# Kivipallur_joonis3.net
KiCad netlist of a schematic drawn in Altium Designer
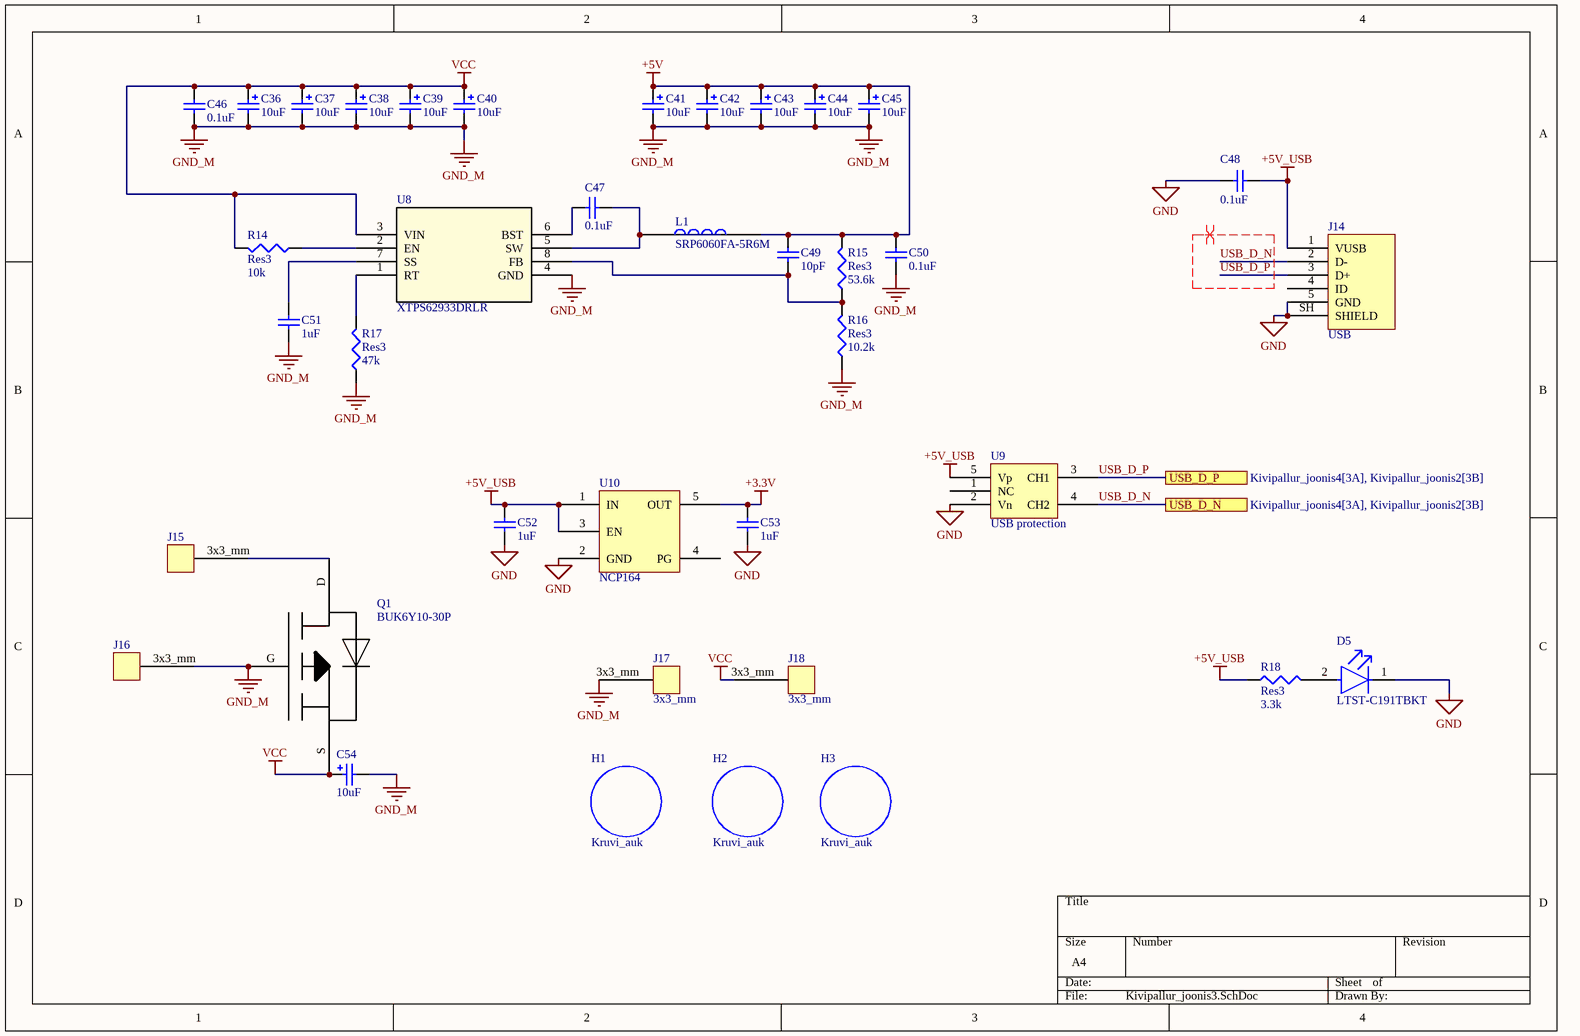
[diagram p0: Kivipallur_joonis3.SchDoc]

(export (version "E")
  (design (tool "Eeschema 10.0.6"))
  (components
    (comp (ref "C36")
      (value "10uF")
      (footprint "C0805")
      (description "Polarized Capacitor (Surface Mount)")
      (fields (field (name "Comment") "Cap Pol3") (field (name "PUBLISHER") "Altium Limited"))
      (libsource (lib "Miscellaneous Devices") (part "Cap Pol3"))
    )
    (comp (ref "C37")
      (value "10uF")
      (footprint "C0805")
      (description "Polarized Capacitor (Surface Mount)")
      (fields (field (name "Comment") "Cap Pol3") (field (name "PUBLISHER") "Altium Limited"))
      (libsource (lib "Miscellaneous Devices") (part "Cap Pol3"))
    )
    (comp (ref "C38")
      (value "10uF")
      (footprint "C0805")
      (description "Polarized Capacitor (Surface Mount)")
      (fields (field (name "Comment") "Cap Pol3") (field (name "PUBLISHER") "Altium Limited"))
      (libsource (lib "Miscellaneous Devices") (part "Cap Pol3"))
    )
    (comp (ref "C39")
      (value "10uF")
      (footprint "C0805")
      (description "Polarized Capacitor (Surface Mount)")
      (fields (field (name "Comment") "Cap Pol3") (field (name "PUBLISHER") "Altium Limited"))
      (libsource (lib "Miscellaneous Devices") (part "Cap Pol3"))
    )
    (comp (ref "C40")
      (value "10uF")
      (footprint "C0805")
      (description "Polarized Capacitor (Surface Mount)")
      (fields (field (name "Comment") "Cap Pol3") (field (name "PUBLISHER") "Altium Limited"))
      (libsource (lib "Miscellaneous Devices") (part "Cap Pol3"))
    )
    (comp (ref "C41")
      (value "10uF")
      (footprint "C0805")
      (description "Polarized Capacitor (Surface Mount)")
      (fields (field (name "Comment") "Cap Pol3") (field (name "PUBLISHER") "Altium Limited"))
      (libsource (lib "Miscellaneous Devices") (part "Cap Pol3"))
    )
    (comp (ref "C42")
      (value "10uF")
      (footprint "C0805")
      (description "Polarized Capacitor (Surface Mount)")
      (fields (field (name "Comment") "Cap Pol3") (field (name "PUBLISHER") "Altium Limited"))
      (libsource (lib "Miscellaneous Devices") (part "Cap Pol3"))
    )
    (comp (ref "C43")
      (value "10uF")
      (footprint "C0805")
      (description "Polarized Capacitor (Surface Mount)")
      (fields (field (name "Comment") "Cap Pol3") (field (name "PUBLISHER") "Altium Limited"))
      (libsource (lib "Miscellaneous Devices") (part "Cap Pol3"))
    )
    (comp (ref "C44")
      (value "10uF")
      (footprint "C0805")
      (description "Polarized Capacitor (Surface Mount)")
      (fields (field (name "Comment") "Cap Pol3") (field (name "PUBLISHER") "Altium Limited"))
      (libsource (lib "Miscellaneous Devices") (part "Cap Pol3"))
    )
    (comp (ref "C45")
      (value "10uF")
      (footprint "C0805")
      (description "Polarized Capacitor (Surface Mount)")
      (fields (field (name "Comment") "Cap Pol3") (field (name "PUBLISHER") "Altium Limited"))
      (libsource (lib "Miscellaneous Devices") (part "Cap Pol3"))
    )
    (comp (ref "C46")
      (value "0.1uF")
      (footprint "1608[0603]")
      (description "Capacitor (Semiconductor SIM Model)")
      (fields (field (name "Comment") "Cap Semi") (field (name "PUBLISHER") "Altium Limited"))
      (libsource (lib "Miscellaneous Devices") (part "Cap Semi"))
    )
    (comp (ref "C47")
      (value "0.1uF")
      (footprint "1608[0603]")
      (description "Capacitor (Semiconductor SIM Model)")
      (fields (field (name "Comment") "Cap Semi") (field (name "PUBLISHER") "Altium Limited"))
      (libsource (lib "Miscellaneous Devices") (part "Cap Semi"))
    )
    (comp (ref "C48")
      (value "0.1uF")
      (footprint "1608[0603]")
      (description "Capacitor (Semiconductor SIM Model)")
      (fields (field (name "Comment") "Cap Semi") (field (name "PUBLISHER") "Altium Limited"))
      (libsource (lib "Miscellaneous Devices") (part "Cap Semi"))
    )
    (comp (ref "C49")
      (value "10pF")
      (footprint "1608[0603]")
      (description "Capacitor (Semiconductor SIM Model)")
      (fields (field (name "Comment") "Cap Semi") (field (name "PUBLISHER") "Altium Limited"))
      (libsource (lib "Miscellaneous Devices") (part "Cap Semi"))
    )
    (comp (ref "C50")
      (value "0.1uF")
      (footprint "1608[0603]")
      (description "Capacitor (Semiconductor SIM Model)")
      (fields (field (name "Comment") "Cap Semi") (field (name "PUBLISHER") "Altium Limited"))
      (libsource (lib "Miscellaneous Devices") (part "Cap Semi"))
    )
    (comp (ref "C51")
      (value "1uF")
      (footprint "1608[0603]")
      (description "Capacitor (Semiconductor SIM Model)")
      (fields (field (name "Comment") "Cap Semi") (field (name "PUBLISHER") "Altium Limited"))
      (libsource (lib "Miscellaneous Devices") (part "Cap Semi"))
    )
    (comp (ref "C52")
      (value "1uF")
      (footprint "1608[0603]")
      (description "Capacitor (Semiconductor SIM Model)")
      (fields (field (name "Comment") "Cap Semi") (field (name "PUBLISHER") "Altium Limited"))
      (libsource (lib "Miscellaneous Devices") (part "Cap Semi"))
    )
    (comp (ref "C53")
      (value "1uF")
      (footprint "1608[0603]")
      (description "Capacitor (Semiconductor SIM Model)")
      (fields (field (name "Comment") "Cap Semi") (field (name "PUBLISHER") "Altium Limited"))
      (libsource (lib "Miscellaneous Devices") (part "Cap Semi"))
    )
    (comp (ref "C54")
      (value "10uF")
      (footprint "C0805")
      (description "Polarized Capacitor (Surface Mount)")
      (fields (field (name "Comment") "Cap Pol3") (field (name "PUBLISHER") "Altium Limited"))
      (libsource (lib "Miscellaneous Devices") (part "Cap Pol3"))
    )
    (comp (ref "D5")
      (value "LTST-C191TBKT")
      (footprint "FP-LTST-C191TBKT-MFG")
      (description "LED BLUE CLEAR CHIP SMD")
      (libsource (lib "Altium Content Vault") (part "8706943c75ba83719d021d2fdc84c58"))
    )
    (comp (ref "H1")
      (value "Kruvi_auk")
      (footprint "kruvi_auk")
      (libsource (lib "kruvi_auk") (part "Kruvi_auk"))
    )
    (comp (ref "H2")
      (value "Kruvi_auk")
      (footprint "kruvi_auk")
      (libsource (lib "kruvi_auk") (part "Kruvi_auk"))
    )
    (comp (ref "H3")
      (value "Kruvi_auk")
      (footprint "kruvi_auk")
      (libsource (lib "kruvi_auk") (part "Kruvi_auk"))
    )
    (comp (ref "J14") (value "USB") (footprint "USB") (libsource (lib "USB") (part "USB")))
    (comp (ref "J15") (value "3x3_mm") (footprint "3x3_mm") (libsource (lib "") (part "3x3_mm_1")))
    (comp (ref "J16") (value "3x3_mm") (footprint "3x3_mm") (libsource (lib "") (part "3x3_mm_1")))
    (comp (ref "J17") (value "3x3_mm") (footprint "3x3_mm") (libsource (lib "3x3_mm") (part "3x3_mm")))
    (comp (ref "J18") (value "3x3_mm") (footprint "3x3_mm") (libsource (lib "3x3_mm") (part "3x3_mm")))
    (comp (ref "L1")
      (value "SRP6060FA-5R6M")
      (footprint "SRP6060FA-5R6M")
      (libsource (lib "SRP6060FA-5R6M") (part "SRP6060FA-5R6M"))
    )
    (comp (ref "Q1")
      (value "BUK6Y10-30P")
      (footprint "BUK6Y10-30P")
      (libsource (lib "BUK6Y10-30P") (part "BUK6Y10-30P"))
    )
    (comp (ref "R14")
      (value "Res3")
      (footprint "J1-0603")
      (description "Resistor")
      (fields (field (name "ALTIUM_VALUE") "10k") (field (name "PUBLISHER") "Altium Limited"))
      (libsource (lib "Miscellaneous Devices") (part "Res3"))
    )
    (comp (ref "R15")
      (value "Res3")
      (footprint "J1-0603")
      (description "Resistor")
      (fields (field (name "ALTIUM_VALUE") "53.6k") (field (name "PUBLISHER") "Altium Limited"))
      (libsource (lib "Miscellaneous Devices") (part "Res3"))
    )
    (comp (ref "R16")
      (value "Res3")
      (footprint "J1-0603")
      (description "Resistor")
      (fields (field (name "ALTIUM_VALUE") "10.2k") (field (name "PUBLISHER") "Altium Limited"))
      (libsource (lib "Miscellaneous Devices") (part "Res3"))
    )
    (comp (ref "R17")
      (value "Res3")
      (footprint "J1-0603")
      (description "Resistor")
      (fields (field (name "ALTIUM_VALUE") "47k") (field (name "PUBLISHER") "Altium Limited"))
      (libsource (lib "Miscellaneous Devices") (part "Res3"))
    )
    (comp (ref "R18")
      (value "Res3")
      (footprint "J1-0603")
      (description "Resistor")
      (fields (field (name "ALTIUM_VALUE") "3.3k") (field (name "PUBLISHER") "Altium Limited"))
      (libsource (lib "Miscellaneous Devices") (part "Res3"))
    )
    (comp (ref "U8")
      (value "XTPS62933DRLR")
      (footprint "SOT_33DRLR_TEX")
      (description "No Description Available")
      (fields (field (name "COPYRIGHT") "Copyright (C) 2022 Ultra Librarian. All rights reserved."))
      (libsource (lib "XTPS62933DRLR") (part "XTPS62933DRLR"))
    )
    (comp (ref "U9")
      (value "USB protection")
      (footprint "USB protection")
      (libsource (lib "USB protection") (part "USB protection"))
    )
    (comp (ref "U10") (value "NCP164") (footprint "NCP164") (libsource (lib "NCP164") (part "NCP164")))
  )
  (nets
    (net (code "1") (name "+3.3V") (class "Default")
      (node (ref "C53") (pin "1") (pinfunction "1_1") (pintype "passive"))
      (node (ref "U10") (pin "5") (pinfunction "OUT_5") (pintype "power_in"))
    )
    (net (code "2") (name "+5V") (class "Default")
      (node (ref "C41") (pin "1") (pinfunction "1_1") (pintype "passive"))
      (node (ref "C42") (pin "1") (pinfunction "1_1") (pintype "passive"))
      (node (ref "C43") (pin "1") (pinfunction "1_1") (pintype "passive"))
      (node (ref "C44") (pin "1") (pinfunction "1_1") (pintype "passive"))
      (node (ref "C45") (pin "1") (pinfunction "1_1") (pintype "passive"))
      (node (ref "C49") (pin "1") (pinfunction "1_1") (pintype "passive"))
      (node (ref "C50") (pin "1") (pinfunction "1_1") (pintype "passive"))
      (node (ref "L1") (pin "2") (pinfunction "2_2") (pintype "passive"))
      (node (ref "R15") (pin "2") (pinfunction "2_2") (pintype "passive"))
    )
    (net (code "3") (name "+5V_USB") (class "Default")
      (node (ref "C48") (pin "1") (pinfunction "1_1") (pintype "passive"))
      (node (ref "C52") (pin "1") (pinfunction "1_1") (pintype "passive"))
      (node (ref "J14") (pin "1") (pinfunction "VUSB_1") (pintype "passive"))
      (node (ref "R18") (pin "1") (pinfunction "1_1") (pintype "passive"))
      (node (ref "U10") (pin "1") (pinfunction "IN_1") (pintype "power_in"))
      (node (ref "U10") (pin "3") (pinfunction "EN_3") (pintype "passive"))
      (node (ref "U9") (pin "5") (pinfunction "Vp_5") (pintype "passive"))
    )
    (net (code "4") (name "/USB_D_N") (class "Default")
      (node (ref "J14") (pin "2") (pinfunction "D-_2") (pintype "passive"))
      (node (ref "U9") (pin "4") (pinfunction "CH2_4") (pintype "passive"))
    )
    (net (code "5") (name "/USB_D_P") (class "Default")
      (node (ref "J14") (pin "3") (pinfunction "D+_3") (pintype "passive"))
      (node (ref "U9") (pin "3") (pinfunction "CH1_3") (pintype "passive"))
    )
    (net (code "6") (name "GND") (class "Default")
      (node (ref "C48") (pin "2") (pinfunction "2_2") (pintype "passive"))
      (node (ref "C52") (pin "2") (pinfunction "2_2") (pintype "passive"))
      (node (ref "C53") (pin "2") (pinfunction "2_2") (pintype "passive"))
      (node (ref "D5") (pin "1") (pinfunction "C_1") (pintype "passive"))
      (node (ref "J14") (pin "5") (pinfunction "GND_5") (pintype "passive"))
      (node (ref "J14") (pin "SH") (pinfunction "SHIELD_SH") (pintype "passive"))
      (node (ref "U10") (pin "2") (pinfunction "GND_2") (pintype "power_in"))
      (node (ref "U9") (pin "2") (pinfunction "Vn_2") (pintype "passive"))
    )
    (net (code "7") (name "GND_M") (class "Default")
      (node (ref "C36") (pin "2") (pinfunction "2_2") (pintype "passive"))
      (node (ref "C37") (pin "2") (pinfunction "2_2") (pintype "passive"))
      (node (ref "C38") (pin "2") (pinfunction "2_2") (pintype "passive"))
      (node (ref "C39") (pin "2") (pinfunction "2_2") (pintype "passive"))
      (node (ref "C40") (pin "2") (pinfunction "2_2") (pintype "passive"))
      (node (ref "C41") (pin "2") (pinfunction "2_2") (pintype "passive"))
      (node (ref "C42") (pin "2") (pinfunction "2_2") (pintype "passive"))
      (node (ref "C43") (pin "2") (pinfunction "2_2") (pintype "passive"))
      (node (ref "C44") (pin "2") (pinfunction "2_2") (pintype "passive"))
      (node (ref "C45") (pin "2") (pinfunction "2_2") (pintype "passive"))
      (node (ref "C46") (pin "2") (pinfunction "2_2") (pintype "passive"))
      (node (ref "C50") (pin "2") (pinfunction "2_2") (pintype "passive"))
      (node (ref "C51") (pin "2") (pinfunction "2_2") (pintype "passive"))
      (node (ref "C54") (pin "2") (pinfunction "2_2") (pintype "passive"))
      (node (ref "J16") (pin "3x3_mm") (pintype "power_in"))
      (node (ref "J17") (pin "3x3_mm") (pintype "power_in"))
      (node (ref "Q1") (pin "G") (pintype "passive"))
      (node (ref "R16") (pin "1") (pinfunction "1_1") (pintype "passive"))
      (node (ref "R17") (pin "1") (pinfunction "1_1") (pintype "passive"))
      (node (ref "U8") (pin "4") (pinfunction "GND_4") (pintype "passive"))
    )
    (net (code "8") (name "Net-(D5-A)") (class "Default")
      (node (ref "D5") (pin "2") (pinfunction "A_2") (pintype "passive"))
      (node (ref "R18") (pin "2") (pinfunction "2_2") (pintype "passive"))
    )
    (net (code "9") (name "Net-(J15-Pad3x3_mm)") (class "Default")
      (node (ref "J15") (pin "3x3_mm") (pintype "power_in"))
      (node (ref "Q1") (pin "D") (pintype "passive"))
    )
    (net (code "10") (name "Net-(U8-BST)") (class "Default")
      (node (ref "C47") (pin "1") (pinfunction "1_1") (pintype "passive"))
      (node (ref "U8") (pin "6") (pinfunction "BST_6") (pintype "passive"))
    )
    (net (code "11") (name "Net-(U8-EN)") (class "Default")
      (node (ref "R14") (pin "1") (pinfunction "1_1") (pintype "passive"))
      (node (ref "U8") (pin "2") (pinfunction "EN_2") (pintype "passive"))
    )
    (net (code "12") (name "Net-(U8-FB)") (class "Default")
      (node (ref "C49") (pin "2") (pinfunction "2_2") (pintype "passive"))
      (node (ref "R15") (pin "1") (pinfunction "1_1") (pintype "passive"))
      (node (ref "R16") (pin "2") (pinfunction "2_2") (pintype "passive"))
      (node (ref "U8") (pin "8") (pinfunction "FB_8") (pintype "passive"))
    )
    (net (code "13") (name "Net-(U8-RT)") (class "Default")
      (node (ref "R17") (pin "2") (pinfunction "2_2") (pintype "passive"))
      (node (ref "U8") (pin "1") (pinfunction "RT_1") (pintype "passive"))
    )
    (net (code "14") (name "Net-(U8-SS)") (class "Default")
      (node (ref "C51") (pin "1") (pinfunction "1_1") (pintype "passive"))
      (node (ref "U8") (pin "7") (pinfunction "SS_7") (pintype "passive"))
    )
    (net (code "15") (name "Net-(U8-SW)") (class "Default")
      (node (ref "C47") (pin "2") (pinfunction "2_2") (pintype "passive"))
      (node (ref "L1") (pin "1") (pinfunction "1_1") (pintype "passive"))
      (node (ref "U8") (pin "5") (pinfunction "SW_5") (pintype "passive"))
    )
    (net (code "16") (name "VCC") (class "Default")
      (node (ref "C36") (pin "1") (pinfunction "1_1") (pintype "passive"))
      (node (ref "C37") (pin "1") (pinfunction "1_1") (pintype "passive"))
      (node (ref "C38") (pin "1") (pinfunction "1_1") (pintype "passive"))
      (node (ref "C39") (pin "1") (pinfunction "1_1") (pintype "passive"))
      (node (ref "C40") (pin "1") (pinfunction "1_1") (pintype "passive"))
      (node (ref "C46") (pin "1") (pinfunction "1_1") (pintype "passive"))
      (node (ref "C54") (pin "1") (pinfunction "1_1") (pintype "passive"))
      (node (ref "J18") (pin "3x3_mm") (pintype "power_in"))
      (node (ref "Q1") (pin "S") (pintype "passive"))
      (node (ref "R14") (pin "2") (pinfunction "2_2") (pintype "passive"))
      (node (ref "U8") (pin "3") (pinfunction "VIN_3") (pintype "passive"))
    )
    (net (code "17") (name "unconnected-(J14-ID-Pad4)") (class "Default")
      (node (ref "J14") (pin "4") (pinfunction "ID_4") (pintype "passive"))
    )
    (net (code "18") (name "unconnected-(U9-NC-Pad1)") (class "Default")
      (node (ref "U9") (pin "1") (pinfunction "NC_1") (pintype "passive"))
    )
    (net (code "19") (name "unconnected-(U10-PG-Pad4)") (class "Default")
      (node (ref "U10") (pin "4") (pinfunction "PG_4") (pintype "passive"))
    )
  )
)
